# ESP_32_BANG_TAI.net
KiCad netlist of a schematic drawn in Altium Designer
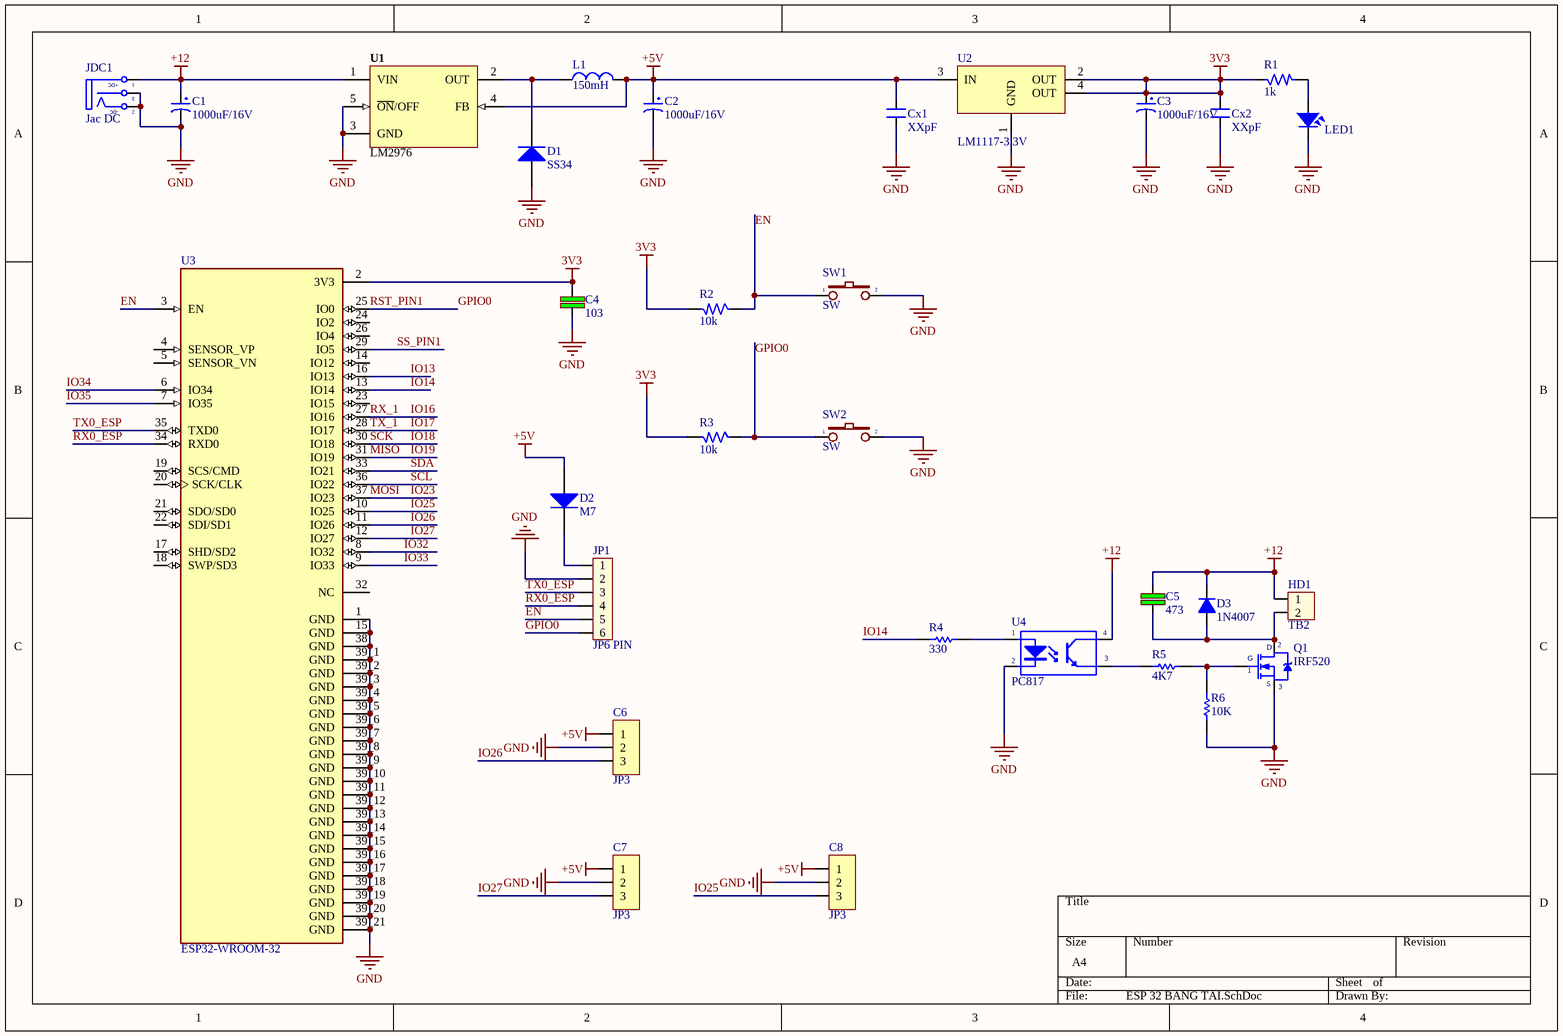
[diagram p0: ESP 32 BANG TAI.SchDoc]

(export (version "E")
  (design (tool "Eeschema 10.0.6"))
  (components
    (comp (ref "C1")
      (value "1000uF/16V")
      (footprint "CP1.5/3.4")
      (description "Cap 1000uF/16V - 220uF/50V")
      (libsource (lib "syhaunguyen") (part "CP4"))
    )
    (comp (ref "C2")
      (value "1000uF/16V")
      (footprint "CP1.5/3.4")
      (description "Cap 1000uF/16V - 220uF/50V")
      (libsource (lib "syhaunguyen") (part "CP4"))
    )
    (comp (ref "C3")
      (value "1000uF/16V")
      (footprint "CP1.5/3.4")
      (description "Cap 1000uF/16V - 220uF/50V")
      (libsource (lib "syhaunguyen") (part "CP4"))
    )
    (comp (ref "C4")
      (value "103")
      (footprint "SM-1206")
      (description "Cap SMD")
      (libsource (lib "Library AL") (part "C"))
    )
    (comp (ref "C5")
      (value "473")
      (footprint "CN3")
      (description "Cap np W0.3")
      (fields (field (name "COPYRIGHT") "VanDungEvn"))
      (libsource (lib "Library AL") (part "CN3"))
    )
    (comp (ref "C6")
      (value "JP3")
      (footprint "JP3-D1T")
      (description "WR-PHD 2.54 mm Angled Socket Header")
      (fields
        (field (name "MANUFACTURER") "Würth Elektronik eiSos GmbH")
        (field (name "PARTNO") "613003143121")
        (field (name "CREATED BY") "Karrer Zheng")
      )
      (libsource (lib "Lib by Quang") (part "JP3"))
    )
    (comp (ref "C7")
      (value "JP3")
      (footprint "JP3-D1T")
      (description "WR-PHD 2.54 mm Angled Socket Header")
      (fields
        (field (name "MANUFACTURER") "Würth Elektronik eiSos GmbH")
        (field (name "PARTNO") "613003143121")
        (field (name "CREATED BY") "Karrer Zheng")
      )
      (libsource (lib "Lib by Quang") (part "JP3"))
    )
    (comp (ref "C8")
      (value "JP3")
      (footprint "JP3-D1T")
      (description "WR-PHD 2.54 mm Angled Socket Header")
      (fields
        (field (name "MANUFACTURER") "Würth Elektronik eiSos GmbH")
        (field (name "PARTNO") "613003143121")
        (field (name "CREATED BY") "Karrer Zheng")
      )
      (libsource (lib "Lib by Quang") (part "JP3"))
    )
    (comp (ref "Cx1") (value "XXpF") (footprint "CN-SMD-1206") (libsource (lib "Lib by Quang") (part "CN")))
    (comp (ref "Cx2") (value "XXpF") (footprint "CN-SMD-1206") (libsource (lib "Lib by Quang") (part "CN")))
    (comp (ref "D1")
      (value "SS34")
      (footprint "DIODE SMA")
      (description "Dán")
      (libsource (lib "Diode") (part "Diode SS34 ( 1N5822 )"))
    )
    (comp (ref "D2")
      (value "M7")
      (footprint "DIODE SMA")
      (description "Dán")
      (libsource (lib "Diode") (part "Diode M7 ( 4007 )"))
    )
    (comp (ref "D3")
      (value "1N4007")
      (footprint "D1A")
      (description "Diode 1A")
      (libsource (lib "Library AL") (part "D1A"))
    )
    (comp (ref "HD1")
      (value "TB2")
      (footprint "HED2T")
      (description "Header 2 (Green)")
      (libsource (lib "Library AL") (part "Hed2"))
    )
    (comp (ref "JDC1")
      (value "Jac DC")
      (footprint "DC-IN")
      (description "Jac DC input")
      (libsource (lib "syhaunguyen") (part "DCIN"))
    )
    (comp (ref "JP1") (value "JP6 PIN") (footprint "JP6") (libsource (lib "syhaunguyen") (part "JP6")))
    (comp (ref "L1")
      (value "150mH")
      (footprint "L01")
      (description "Inductor")
      (libsource (lib "Library AL") (part "Inductor"))
    )
    (comp (ref "LED1")
      (value "LED SMD")
      (footprint "SM-LED-1206-Blue")
      (libsource (lib "Lib by Quang") (part "LED-SMD-1206"))
    )
    (comp (ref "Q1")
      (value "IRF520")
      (footprint "QTO-220")
      (description "MOSFET N - CHANNEL 500V - 0.75 - 8A - TO-220")
      (libsource (lib "syhaunguyen") (part "IRF840"))
    )
    (comp (ref "R1")
      (value "1k")
      (footprint "SM-RES-1206")
      (description "Resistor 1/4W")
      (libsource (lib "Lib by Quang") (part "R"))
    )
    (comp (ref "R2")
      (value "10k")
      (footprint "SM-RES-1206")
      (description "Resistor 1/4W")
      (libsource (lib "syhaunguyen") (part "R"))
    )
    (comp (ref "R3")
      (value "10k")
      (footprint "SM-RES-1206")
      (description "Resistor 1/4W")
      (libsource (lib "syhaunguyen") (part "R"))
    )
    (comp (ref "R4")
      (value "330")
      (footprint "R1/4W")
      (description "Resistor")
      (fields
        (field (name "MANUFACTURER") "Generic Components")
        (field (name "Comment") "Res1")
        (field (name "PUBLISHER") "Altium Hobart Technology Centre")
      )
      (libsource (lib "syhaunguyen") (part "Res1_1"))
    )
    (comp (ref "R5")
      (value "4K7")
      (footprint "R1/4W")
      (description "Resistor")
      (fields
        (field (name "MANUFACTURER") "Generic Components")
        (field (name "Comment") "Res1")
        (field (name "PUBLISHER") "Altium Hobart Technology Centre")
      )
      (libsource (lib "syhaunguyen") (part "Res1_1"))
    )
    (comp (ref "R6")
      (value "10K")
      (footprint "R1/4W")
      (description "Resistor")
      (fields
        (field (name "MANUFACTURER") "Generic Components")
        (field (name "Comment") "Res1")
        (field (name "PUBLISHER") "Altium Hobart Technology Centre")
      )
      (libsource (lib "syhaunguyen") (part "Res1_1"))
    )
    (comp (ref "SW1")
      (value "SW")
      (footprint "SW1-SMD")
      (description "Switch button 2 pin")
      (libsource (lib "Lib by Quang") (part "SW2"))
    )
    (comp (ref "SW2")
      (value "SW")
      (footprint "SW1-SMD")
      (description "Switch button 2 pin")
      (libsource (lib "Lib by Quang") (part "SW2"))
    )
    (comp (ref "U1") (value "LM2976") (footprint "DIP5") (libsource (lib "LIBRARY") (part "LM2596")))
    (comp (ref "U2")
      (value "LM1117-3.3V")
      (footprint "SOT223-4.CAOVANHUONG")
      (description "800mA Low-Dropout Linear Regulator")
      (fields (field (name "CREATOR") "Nguyen Ba Bien"))
      (libsource (lib "Lib by Quang") (part "LM1117"))
    )
    (comp (ref "U3")
      (value "ESP32-WROOM-32")
      (footprint "MODULE_ESP32-WROOM-32")
      (fields (field (name "MF") "Espressif Systems"))
      (libsource (lib "ESP32-WROOM-32") (part "ESP32-WROOM-32"))
    )
    (comp (ref "U4")
      (value "PC817")
      (footprint "DIP4/W0.3")
      (description "Single Opto")
      (libsource (lib "syhaunguyen") (part "PC817"))
    )
  )
  (nets
    (net (code "1") (name "+5V") (class "Default")
      (node (ref "C2") (pin "1") (pinfunction "1_1") (pintype "passive"))
      (node (ref "C6") (pin "1") (pinfunction "1_1") (pintype "passive"))
      (node (ref "C7") (pin "1") (pinfunction "1_1") (pintype "passive"))
      (node (ref "C8") (pin "1") (pinfunction "1_1") (pintype "passive"))
      (node (ref "Cx1") (pin "2") (pinfunction "2_2") (pintype "passive"))
      (node (ref "D2") (pin "1") (pinfunction "A_1") (pintype "passive"))
      (node (ref "L1") (pin "2") (pinfunction "2_2") (pintype "passive"))
      (node (ref "U1") (pin "4") (pinfunction "FB_4") (pintype "input"))
      (node (ref "U2") (pin "3") (pinfunction "IN_3") (pintype "passive"))
    )
    (net (code "2") (name "+12") (class "Default")
      (node (ref "C1") (pin "1") (pinfunction "1_1") (pintype "passive"))
      (node (ref "C5") (pin "2") (pinfunction "2_2") (pintype "passive"))
      (node (ref "D3") (pin "2") (pinfunction "K_2") (pintype "passive"))
      (node (ref "HD1") (pin "1") (pinfunction "1_1") (pintype "passive"))
      (node (ref "JDC1") (pin "1") (pinfunction "T_1") (pintype "passive"))
      (node (ref "U1") (pin "1") (pinfunction "VIN_1") (pintype "power_in"))
      (node (ref "U4") (pin "4") (pinfunction "C_4") (pintype "passive"))
    )
    (net (code "3") (name "/EN") (class "Default")
      (node (ref "JP1") (pin "5") (pinfunction "5_5") (pintype "passive"))
      (node (ref "R2") (pin "1") (pinfunction "1_1") (pintype "passive"))
      (node (ref "SW1") (pin "1") (pinfunction "1_1") (pintype "passive"))
      (node (ref "U3") (pin "3") (pinfunction "EN_3") (pintype "input"))
    )
    (net (code "4") (name "/GPIO0") (class "Default")
      (node (ref "JP1") (pin "6") (pinfunction "6_6") (pintype "passive"))
      (node (ref "R3") (pin "1") (pinfunction "1_1") (pintype "passive"))
      (node (ref "SW2") (pin "1") (pinfunction "1_1") (pintype "passive"))
      (node (ref "U3") (pin "25") (pinfunction "IO0_25") (pintype "bidirectional"))
    )
    (net (code "5") (name "/IO13") (class "Default")
      (node (ref "U3") (pin "16") (pinfunction "IO13_16") (pintype "bidirectional"))
    )
    (net (code "6") (name "/IO14") (class "Default")
      (node (ref "R4") (pin "1") (pinfunction "1_1") (pintype "passive"))
      (node (ref "U3") (pin "13") (pinfunction "IO14_13") (pintype "bidirectional"))
    )
    (net (code "7") (name "/IO16") (class "Default")
      (node (ref "U3") (pin "27") (pinfunction "IO16_27") (pintype "bidirectional"))
    )
    (net (code "8") (name "/IO17") (class "Default")
      (node (ref "U3") (pin "28") (pinfunction "IO17_28") (pintype "bidirectional"))
    )
    (net (code "9") (name "/IO18") (class "Default")
      (node (ref "U3") (pin "30") (pinfunction "IO18_30") (pintype "bidirectional"))
    )
    (net (code "10") (name "/IO19") (class "Default")
      (node (ref "U3") (pin "31") (pinfunction "IO19_31") (pintype "bidirectional"))
    )
    (net (code "11") (name "/IO23") (class "Default")
      (node (ref "U3") (pin "37") (pinfunction "IO23_37") (pintype "bidirectional"))
    )
    (net (code "12") (name "/IO25") (class "Default")
      (node (ref "C8") (pin "3") (pinfunction "3_3") (pintype "passive"))
      (node (ref "U3") (pin "10") (pinfunction "IO25_10") (pintype "bidirectional"))
    )
    (net (code "13") (name "/IO26") (class "Default")
      (node (ref "C6") (pin "3") (pinfunction "3_3") (pintype "passive"))
      (node (ref "U3") (pin "11") (pinfunction "IO26_11") (pintype "bidirectional"))
    )
    (net (code "14") (name "/IO27") (class "Default")
      (node (ref "C7") (pin "3") (pinfunction "3_3") (pintype "passive"))
      (node (ref "U3") (pin "12") (pinfunction "IO27_12") (pintype "bidirectional"))
    )
    (net (code "15") (name "/IO32") (class "Default")
      (node (ref "U3") (pin "8") (pinfunction "IO32_8") (pintype "bidirectional"))
    )
    (net (code "16") (name "/IO33") (class "Default")
      (node (ref "U3") (pin "9") (pinfunction "IO33_9") (pintype "bidirectional"))
    )
    (net (code "17") (name "/IO34") (class "Default")
      (node (ref "U3") (pin "6") (pinfunction "IO34_6") (pintype "input"))
    )
    (net (code "18") (name "/IO35") (class "Default")
      (node (ref "U3") (pin "7") (pinfunction "IO35_7") (pintype "input"))
    )
    (net (code "19") (name "/RX0_ESP") (class "Default")
      (node (ref "JP1") (pin "4") (pinfunction "4_4") (pintype "passive"))
      (node (ref "U3") (pin "34") (pinfunction "RXD0_34") (pintype "bidirectional"))
    )
    (net (code "20") (name "/SCL") (class "Default")
      (node (ref "U3") (pin "36") (pinfunction "IO22_36") (pintype "bidirectional"))
    )
    (net (code "21") (name "/SDA") (class "Default")
      (node (ref "U3") (pin "33") (pinfunction "IO21_33") (pintype "bidirectional"))
    )
    (net (code "22") (name "/SS_PIN1") (class "Default")
      (node (ref "U3") (pin "29") (pinfunction "IO5_29") (pintype "bidirectional"))
    )
    (net (code "23") (name "/TX0_ESP") (class "Default")
      (node (ref "JP1") (pin "3") (pinfunction "3_3") (pintype "passive"))
      (node (ref "U3") (pin "35") (pinfunction "TXD0_35") (pintype "bidirectional"))
    )
    (net (code "24") (name "3V3") (class "Default")
      (node (ref "C3") (pin "1") (pinfunction "1_1") (pintype "passive"))
      (node (ref "C4") (pin "1") (pinfunction "1_1") (pintype "passive"))
      (node (ref "Cx2") (pin "2") (pinfunction "2_2") (pintype "passive"))
      (node (ref "R1") (pin "1") (pinfunction "1_1") (pintype "passive"))
      (node (ref "R2") (pin "2") (pinfunction "2_2") (pintype "passive"))
      (node (ref "R3") (pin "2") (pinfunction "2_2") (pintype "passive"))
      (node (ref "U2") (pin "2") (pinfunction "OUT_2") (pintype "passive"))
      (node (ref "U2") (pin "4") (pinfunction "OUT_4") (pintype "passive"))
      (node (ref "U3") (pin "2") (pinfunction "3V3_2") (pintype "power_in"))
    )
    (net (code "25") (name "GND") (class "Default")
      (node (ref "C1") (pin "2") (pinfunction "2_2") (pintype "passive"))
      (node (ref "C2") (pin "2") (pinfunction "2_2") (pintype "passive"))
      (node (ref "C3") (pin "2") (pinfunction "2_2") (pintype "passive"))
      (node (ref "C4") (pin "2") (pinfunction "2_2") (pintype "passive"))
      (node (ref "C6") (pin "2") (pinfunction "2_2") (pintype "passive"))
      (node (ref "C7") (pin "2") (pinfunction "2_2") (pintype "passive"))
      (node (ref "C8") (pin "2") (pinfunction "2_2") (pintype "passive"))
      (node (ref "Cx1") (pin "1") (pinfunction "1_1") (pintype "passive"))
      (node (ref "Cx2") (pin "1") (pinfunction "1_1") (pintype "passive"))
      (node (ref "D1") (pin "1") (pinfunction "A_1") (pintype "passive"))
      (node (ref "JDC1") (pin "2") (pinfunction "TN_2") (pintype "passive"))
      (node (ref "JDC1") (pin "3") (pinfunction "S_3") (pintype "power_in"))
      (node (ref "JP1") (pin "2") (pinfunction "2_2") (pintype "passive"))
      (node (ref "LED1") (pin "2") (pinfunction "2_2") (pintype "passive"))
      (node (ref "Q1") (pin "3") (pinfunction "S_3") (pintype "passive"))
      (node (ref "R6") (pin "1") (pinfunction "1_1") (pintype "passive"))
      (node (ref "SW1") (pin "2") (pinfunction "2_2") (pintype "passive"))
      (node (ref "SW2") (pin "2") (pinfunction "2_2") (pintype "passive"))
      (node (ref "U1") (pin "3") (pinfunction "GND_3") (pintype "power_in"))
      (node (ref "U1") (pin "5") (pinfunction "~{ON}/OFF_5") (pintype "input"))
      (node (ref "U2") (pin "1") (pinfunction "GND_1") (pintype "passive"))
      (node (ref "U3") (pin "1") (pinfunction "GND_1") (pintype "power_in"))
      (node (ref "U3") (pin "15") (pinfunction "GND_15") (pintype "power_in"))
      (node (ref "U3") (pin "38") (pinfunction "GND_38") (pintype "power_in"))
      (node (ref "U3") (pin "39_1") (pinfunction "GND_39_1") (pintype "power_in"))
      (node (ref "U3") (pin "39_10") (pinfunction "GND_39_10") (pintype "power_in"))
      (node (ref "U3") (pin "39_11") (pinfunction "GND_39_11") (pintype "power_in"))
      (node (ref "U3") (pin "39_12") (pinfunction "GND_39_12") (pintype "power_in"))
      (node (ref "U3") (pin "39_13") (pinfunction "GND_39_13") (pintype "power_in"))
      (node (ref "U3") (pin "39_14") (pinfunction "GND_39_14") (pintype "power_in"))
      (node (ref "U3") (pin "39_15") (pinfunction "GND_39_15") (pintype "power_in"))
      (node (ref "U3") (pin "39_16") (pinfunction "GND_39_16") (pintype "power_in"))
      (node (ref "U3") (pin "39_17") (pinfunction "GND_39_17") (pintype "power_in"))
      (node (ref "U3") (pin "39_18") (pinfunction "GND_39_18") (pintype "power_in"))
      (node (ref "U3") (pin "39_19") (pinfunction "GND_39_19") (pintype "power_in"))
      (node (ref "U3") (pin "39_2") (pinfunction "GND_39_2") (pintype "power_in"))
      (node (ref "U3") (pin "39_20") (pinfunction "GND_39_20") (pintype "power_in"))
      (node (ref "U3") (pin "39_21") (pinfunction "GND_39_21") (pintype "power_in"))
      (node (ref "U3") (pin "39_3") (pinfunction "GND_39_3") (pintype "power_in"))
      (node (ref "U3") (pin "39_4") (pinfunction "GND_39_4") (pintype "power_in"))
      (node (ref "U3") (pin "39_5") (pinfunction "GND_39_5") (pintype "power_in"))
      (node (ref "U3") (pin "39_6") (pinfunction "GND_39_6") (pintype "power_in"))
      (node (ref "U3") (pin "39_7") (pinfunction "GND_39_7") (pintype "power_in"))
      (node (ref "U3") (pin "39_8") (pinfunction "GND_39_8") (pintype "power_in"))
      (node (ref "U3") (pin "39_9") (pinfunction "GND_39_9") (pintype "power_in"))
      (node (ref "U4") (pin "2") (pinfunction "K_2") (pintype "passive"))
    )
    (net (code "26") (name "Net-(D1-K)") (class "Default")
      (node (ref "D1") (pin "2") (pinfunction "K_2") (pintype "passive"))
      (node (ref "L1") (pin "1") (pinfunction "1_1") (pintype "passive"))
      (node (ref "U1") (pin "2") (pinfunction "OUT_2") (pintype "power_in"))
    )
    (net (code "27") (name "Net-(D2-K)") (class "Default")
      (node (ref "D2") (pin "2") (pinfunction "K_2") (pintype "passive"))
      (node (ref "JP1") (pin "1") (pinfunction "1_1") (pintype "passive"))
    )
    (net (code "28") (name "Net-(D3-A)") (class "Default")
      (node (ref "C5") (pin "1") (pinfunction "1_1") (pintype "passive"))
      (node (ref "D3") (pin "1") (pinfunction "A_1") (pintype "passive"))
      (node (ref "HD1") (pin "2") (pinfunction "2_2") (pintype "passive"))
      (node (ref "Q1") (pin "2") (pinfunction "D_2") (pintype "passive"))
    )
    (net (code "29") (name "Net-(LED1-Pad1)") (class "Default")
      (node (ref "LED1") (pin "1") (pinfunction "1_1") (pintype "passive"))
      (node (ref "R1") (pin "2") (pinfunction "2_2") (pintype "passive"))
    )
    (net (code "30") (name "Net-(Q1-G)") (class "Default")
      (node (ref "Q1") (pin "1") (pinfunction "G_1") (pintype "passive"))
      (node (ref "R5") (pin "2") (pinfunction "2_2") (pintype "passive"))
      (node (ref "R6") (pin "2") (pinfunction "2_2") (pintype "passive"))
    )
    (net (code "31") (name "Net-(U4-A)") (class "Default")
      (node (ref "R4") (pin "2") (pinfunction "2_2") (pintype "passive"))
      (node (ref "U4") (pin "1") (pinfunction "A_1") (pintype "passive"))
    )
    (net (code "32") (name "Net-(U4-E)") (class "Default")
      (node (ref "R5") (pin "1") (pinfunction "1_1") (pintype "passive"))
      (node (ref "U4") (pin "3") (pinfunction "E_3") (pintype "passive"))
    )
    (net (code "33") (name "unconnected-(U3-IO2-Pad24)") (class "Default")
      (node (ref "U3") (pin "24") (pinfunction "IO2_24") (pintype "bidirectional"))
    )
    (net (code "34") (name "unconnected-(U3-IO4-Pad26)") (class "Default")
      (node (ref "U3") (pin "26") (pinfunction "IO4_26") (pintype "bidirectional"))
    )
    (net (code "35") (name "unconnected-(U3-IO12-Pad14)") (class "Default")
      (node (ref "U3") (pin "14") (pinfunction "IO12_14") (pintype "bidirectional"))
    )
    (net (code "36") (name "unconnected-(U3-IO15-Pad23)") (class "Default")
      (node (ref "U3") (pin "23") (pinfunction "IO15_23") (pintype "bidirectional"))
    )
    (net (code "37") (name "unconnected-(U3-NC-Pad32)") (class "Default")
      (node (ref "U3") (pin "32") (pinfunction "NC_32") (pintype "passive"))
    )
    (net (code "38") (name "unconnected-(U3-SCK{slash}CLK-Pad20)") (class "Default")
      (node (ref "U3") (pin "20") (pinfunction "SCK/CLK_20") (pintype "bidirectional"))
    )
    (net (code "39") (name "unconnected-(U3-SCS{slash}CMD-Pad19)") (class "Default")
      (node (ref "U3") (pin "19") (pinfunction "SCS/CMD_19") (pintype "bidirectional"))
    )
    (net (code "40") (name "unconnected-(U3-SDI{slash}SD1-Pad22)") (class "Default")
      (node (ref "U3") (pin "22") (pinfunction "SDI/SD1_22") (pintype "bidirectional"))
    )
    (net (code "41") (name "unconnected-(U3-SDO{slash}SD0-Pad21)") (class "Default")
      (node (ref "U3") (pin "21") (pinfunction "SDO/SD0_21") (pintype "bidirectional"))
    )
    (net (code "42") (name "unconnected-(U3-SENSOR_VN-Pad5)") (class "Default")
      (node (ref "U3") (pin "5") (pinfunction "SENSOR_VN_5") (pintype "input"))
    )
    (net (code "43") (name "unconnected-(U3-SENSOR_VP-Pad4)") (class "Default")
      (node (ref "U3") (pin "4") (pinfunction "SENSOR_VP_4") (pintype "input"))
    )
    (net (code "44") (name "unconnected-(U3-SHD{slash}SD2-Pad17)") (class "Default")
      (node (ref "U3") (pin "17") (pinfunction "SHD/SD2_17") (pintype "bidirectional"))
    )
    (net (code "45") (name "unconnected-(U3-SWP{slash}SD3-Pad18)") (class "Default")
      (node (ref "U3") (pin "18") (pinfunction "SWP/SD3_18") (pintype "bidirectional"))
    )
  )
)
